# tiny13_charlie4_50mm_2xAAA_optical_diag.net
KiCad netlist of a schematic drawn in EAGLE
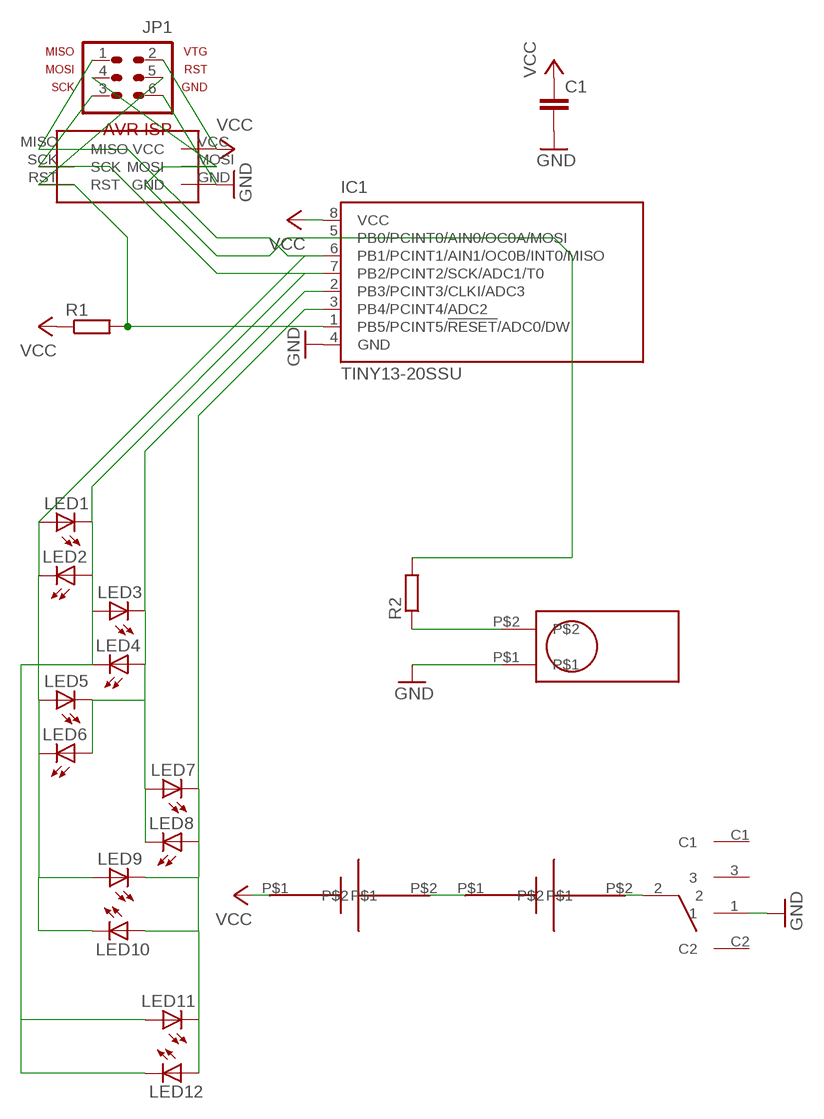
[diagram p0: schematic, sheet 1]

(export (version "E")
  (design (tool "Eeschema 10.0.6"))
  (components
    (comp (ref "C1")
      (value "C-EU025-025X050")
      (footprint "eagle-import:C025-025X050")
      (libsource (lib "eagle-import") (part "C-EU025-025X050"))
    )
    (comp (ref "IC1")
      (value "TINY13-20SSU")
      (footprint "eagle-import:8S1")
      (fields (field (name "MPN") "ATTINY13-20SSU"))
      (libsource (lib "eagle-import") (part "TINY13SSU-20"))
    )
    (comp (ref "JP1")
      (value "AVR-ISP-6")
      (footprint "eagle-import:AVR-ISP-6")
      (libsource (lib "eagle-import") (part "AVR-ISP-6"))
    )
    (comp (ref "LED1")
      (value "LED3MM")
      (footprint "eagle-import:LED3MM")
      (libsource (lib "eagle-import") (part "LED3MM"))
    )
    (comp (ref "LED2")
      (value "LED3MM")
      (footprint "eagle-import:LED3MM")
      (libsource (lib "eagle-import") (part "LED3MM"))
    )
    (comp (ref "LED3")
      (value "LED3MM")
      (footprint "eagle-import:LED3MM")
      (libsource (lib "eagle-import") (part "LED3MM"))
    )
    (comp (ref "LED4")
      (value "LED3MM")
      (footprint "eagle-import:LED3MM")
      (libsource (lib "eagle-import") (part "LED3MM"))
    )
    (comp (ref "LED5")
      (value "LED3MM")
      (footprint "eagle-import:LED3MM")
      (libsource (lib "eagle-import") (part "LED3MM"))
    )
    (comp (ref "LED6")
      (value "LED3MM")
      (footprint "eagle-import:LED3MM")
      (libsource (lib "eagle-import") (part "LED3MM"))
    )
    (comp (ref "LED7")
      (value "LED3MM")
      (footprint "eagle-import:LED3MM")
      (libsource (lib "eagle-import") (part "LED3MM"))
    )
    (comp (ref "LED8")
      (value "LED3MM")
      (footprint "eagle-import:LED3MM")
      (libsource (lib "eagle-import") (part "LED3MM"))
    )
    (comp (ref "LED9")
      (value "LED3MM")
      (footprint "eagle-import:LED3MM")
      (libsource (lib "eagle-import") (part "LED3MM"))
    )
    (comp (ref "LED10")
      (value "LED3MM")
      (footprint "eagle-import:LED3MM")
      (libsource (lib "eagle-import") (part "LED3MM"))
    )
    (comp (ref "LED11")
      (value "LED3MM")
      (footprint "eagle-import:LED3MM")
      (libsource (lib "eagle-import") (part "LED3MM"))
    )
    (comp (ref "LED12")
      (value "LED3MM")
      (footprint "eagle-import:LED3MM")
      (libsource (lib "eagle-import") (part "LED3MM"))
    )
    (comp (ref "R1")
      (value "R-EU_0204/5")
      (footprint "eagle-import:0204_5")
      (libsource (lib "eagle-import") (part "R-EU_0204/5"))
    )
    (comp (ref "R2")
      (value "R-EU_0204/5")
      (footprint "eagle-import:0204_5")
      (libsource (lib "eagle-import") (part "R-EU_0204/5"))
    )
    (comp (ref "U$1")
      (value "TILT_SWITCH_WRAP")
      (footprint "eagle-import:TILT_SWITCH_VAR")
      (libsource (lib "eagle-import") (part "TILT_SWITCH_WRAP"))
    )
    (comp (ref "U$2")
      (value "AVR_ISP_6_PIN_1X6_SMT_CONTACT_BIG")
      (footprint "eagle-import:CONTACT_ISP_PROGRAMMER_1X6_ATMEL")
      (libsource (lib "eagle-import") (part "AVR_ISP_6_PIN_1X6_SMT_CONTACT_BIG"))
    )
    (comp (ref "U$3")
      (value "1XAAA")
      (footprint "eagle-import:AAA_THROUGH_HOLE")
      (libsource (lib "eagle-import") (part "1XAAA"))
    )
    (comp (ref "U$4")
      (value "SWITCH")
      (footprint "eagle-import:SWITCH")
      (libsource (lib "eagle-import") (part "SWITCH"))
    )
    (comp (ref "U$5")
      (value "1XAAA")
      (footprint "eagle-import:AAA_THROUGH_HOLE")
      (libsource (lib "eagle-import") (part "1XAAA"))
    )
  )
  (nets
    (net (code "1") (name "GND") (class "Default")
      (node (ref "C1") (pin "2") (pinfunction "2_2") (pintype "passive"))
      (node (ref "IC1") (pin "4") (pinfunction "GND_4") (pintype "power_in"))
      (node (ref "JP1") (pin "6") (pinfunction "6_6") (pintype "passive"))
      (node (ref "U$1") (pin "P$1") (pinfunction "P$1_P$1") (pintype "bidirectional"))
      (node (ref "U$2") (pin "GND") (pinfunction "GND_GND") (pintype "bidirectional"))
      (node (ref "U$4") (pin "1") (pinfunction "1_1") (pintype "bidirectional"))
    )
    (net (code "2") (name "Net-(IC1-PB0{slash}PCINT0{slash}AIN0{slash}OC0A{slash}MOSI)") (class "Default")
      (node (ref "IC1") (pin "5") (pinfunction "PB0/PCINT0/AIN0/OC0A/MOSI_5") (pintype "bidirectional"))
      (node (ref "JP1") (pin "4") (pinfunction "4_4") (pintype "passive"))
      (node (ref "R2") (pin "2") (pinfunction "2_2") (pintype "passive"))
      (node (ref "U$2") (pin "MOSI") (pinfunction "MOSI_MOSI") (pintype "bidirectional"))
    )
    (net (code "3") (name "Net-(IC1-PB1{slash}PCINT1{slash}AIN1{slash}OC0B{slash}INT0{slash}MISO)") (class "Default")
      (node (ref "IC1") (pin "6") (pinfunction "PB1/PCINT1/AIN1/OC0B/INT0/MISO_6") (pintype "bidirectional"))
      (node (ref "JP1") (pin "1") (pinfunction "1_1") (pintype "passive"))
      (node (ref "LED1") (pin "A") (pinfunction "A_A") (pintype "passive"))
      (node (ref "LED10") (pin "K") (pinfunction "C_K") (pintype "passive"))
      (node (ref "LED2") (pin "K") (pinfunction "C_K") (pintype "passive"))
      (node (ref "LED5") (pin "A") (pinfunction "A_A") (pintype "passive"))
      (node (ref "LED6") (pin "K") (pinfunction "C_K") (pintype "passive"))
      (node (ref "LED9") (pin "A") (pinfunction "A_A") (pintype "passive"))
      (node (ref "U$2") (pin "MISO") (pinfunction "MISO_MISO") (pintype "bidirectional"))
    )
    (net (code "4") (name "Net-(IC1-PB2{slash}PCINT2{slash}SCK{slash}ADC1{slash}T0)") (class "Default")
      (node (ref "IC1") (pin "7") (pinfunction "PB2/PCINT2/SCK/ADC1/T0_7") (pintype "bidirectional"))
      (node (ref "JP1") (pin "3") (pinfunction "3_3") (pintype "passive"))
      (node (ref "LED1") (pin "K") (pinfunction "C_K") (pintype "passive"))
      (node (ref "LED11") (pin "A") (pinfunction "A_A") (pintype "passive"))
      (node (ref "LED12") (pin "K") (pinfunction "C_K") (pintype "passive"))
      (node (ref "LED2") (pin "A") (pinfunction "A_A") (pintype "passive"))
      (node (ref "LED3") (pin "A") (pinfunction "A_A") (pintype "passive"))
      (node (ref "LED4") (pin "K") (pinfunction "C_K") (pintype "passive"))
      (node (ref "U$2") (pin "SCK") (pinfunction "SCK_SCK") (pintype "bidirectional"))
    )
    (net (code "5") (name "Net-(IC1-PB3{slash}PCINT3{slash}CLKI{slash}ADC3)") (class "Default")
      (node (ref "IC1") (pin "2") (pinfunction "PB3/PCINT3/CLKI/ADC3_2") (pintype "bidirectional"))
      (node (ref "LED3") (pin "K") (pinfunction "C_K") (pintype "passive"))
      (node (ref "LED4") (pin "A") (pinfunction "A_A") (pintype "passive"))
      (node (ref "LED5") (pin "K") (pinfunction "C_K") (pintype "passive"))
      (node (ref "LED6") (pin "A") (pinfunction "A_A") (pintype "passive"))
      (node (ref "LED7") (pin "A") (pinfunction "A_A") (pintype "passive"))
      (node (ref "LED8") (pin "K") (pinfunction "C_K") (pintype "passive"))
    )
    (net (code "6") (name "Net-(IC1-PB4{slash}PCINT4{slash}ADC2)") (class "Default")
      (node (ref "IC1") (pin "3") (pinfunction "PB4/PCINT4/ADC2_3") (pintype "bidirectional"))
      (node (ref "LED10") (pin "A") (pinfunction "A_A") (pintype "passive"))
      (node (ref "LED11") (pin "K") (pinfunction "C_K") (pintype "passive"))
      (node (ref "LED12") (pin "A") (pinfunction "A_A") (pintype "passive"))
      (node (ref "LED7") (pin "K") (pinfunction "C_K") (pintype "passive"))
      (node (ref "LED8") (pin "A") (pinfunction "A_A") (pintype "passive"))
      (node (ref "LED9") (pin "K") (pinfunction "C_K") (pintype "passive"))
    )
    (net (code "7") (name "Net-(IC1-PB5{slash}PCINT5{slash}~{RESET}{slash}ADC0{slash}DW)") (class "Default")
      (node (ref "IC1") (pin "1") (pinfunction "PB5/PCINT5/~{RESET}/ADC0/DW_1") (pintype "bidirectional"))
      (node (ref "JP1") (pin "5") (pinfunction "5_5") (pintype "passive"))
      (node (ref "R1") (pin "2") (pinfunction "2_2") (pintype "passive"))
      (node (ref "U$2") (pin "RST") (pinfunction "RST_RST") (pintype "bidirectional"))
    )
    (net (code "8") (name "Net-(R2-Pad1)") (class "Default")
      (node (ref "R2") (pin "1") (pinfunction "1_1") (pintype "passive"))
      (node (ref "U$1") (pin "P$2") (pinfunction "P$2_P$2") (pintype "bidirectional"))
    )
    (net (code "9") (name "Net-(U$3-P$1)") (class "Default")
      (node (ref "U$3") (pin "P$2") (pinfunction "P$1_P$2") (pintype "bidirectional"))
      (node (ref "U$5") (pin "P$1") (pinfunction "P$2_P$1") (pintype "bidirectional"))
    )
    (net (code "10") (name "Net-(U$5-P$1)") (class "Default")
      (node (ref "U$4") (pin "2") (pinfunction "2_2") (pintype "bidirectional"))
      (node (ref "U$5") (pin "P$2") (pinfunction "P$1_P$2") (pintype "bidirectional"))
    )
    (net (code "11") (name "VCC") (class "Default")
      (node (ref "C1") (pin "1") (pinfunction "1_1") (pintype "passive"))
      (node (ref "IC1") (pin "8") (pinfunction "VCC_8") (pintype "power_in"))
      (node (ref "JP1") (pin "2") (pinfunction "2_2") (pintype "passive"))
      (node (ref "R1") (pin "1") (pinfunction "1_1") (pintype "passive"))
      (node (ref "U$2") (pin "VCC") (pinfunction "VCC_VCC") (pintype "bidirectional"))
      (node (ref "U$3") (pin "P$1") (pinfunction "P$2_P$1") (pintype "bidirectional"))
    )
    (net (code "12") (name "unconnected-(U$4-Pad3)") (class "Default")
      (node (ref "U$4") (pin "3") (pinfunction "3_3") (pintype "bidirectional"))
    )
    (net (code "13") (name "unconnected-(U$4-PadC1)") (class "Default")
      (node (ref "U$4") (pin "C1") (pinfunction "C1_C1") (pintype "bidirectional"))
    )
    (net (code "14") (name "unconnected-(U$4-PadC2)") (class "Default")
      (node (ref "U$4") (pin "C2") (pinfunction "C2_C2") (pintype "bidirectional"))
    )
  )
)
